# 10_-_ETHERNET.net
KiCad netlist of a schematic drawn in Altium Designer
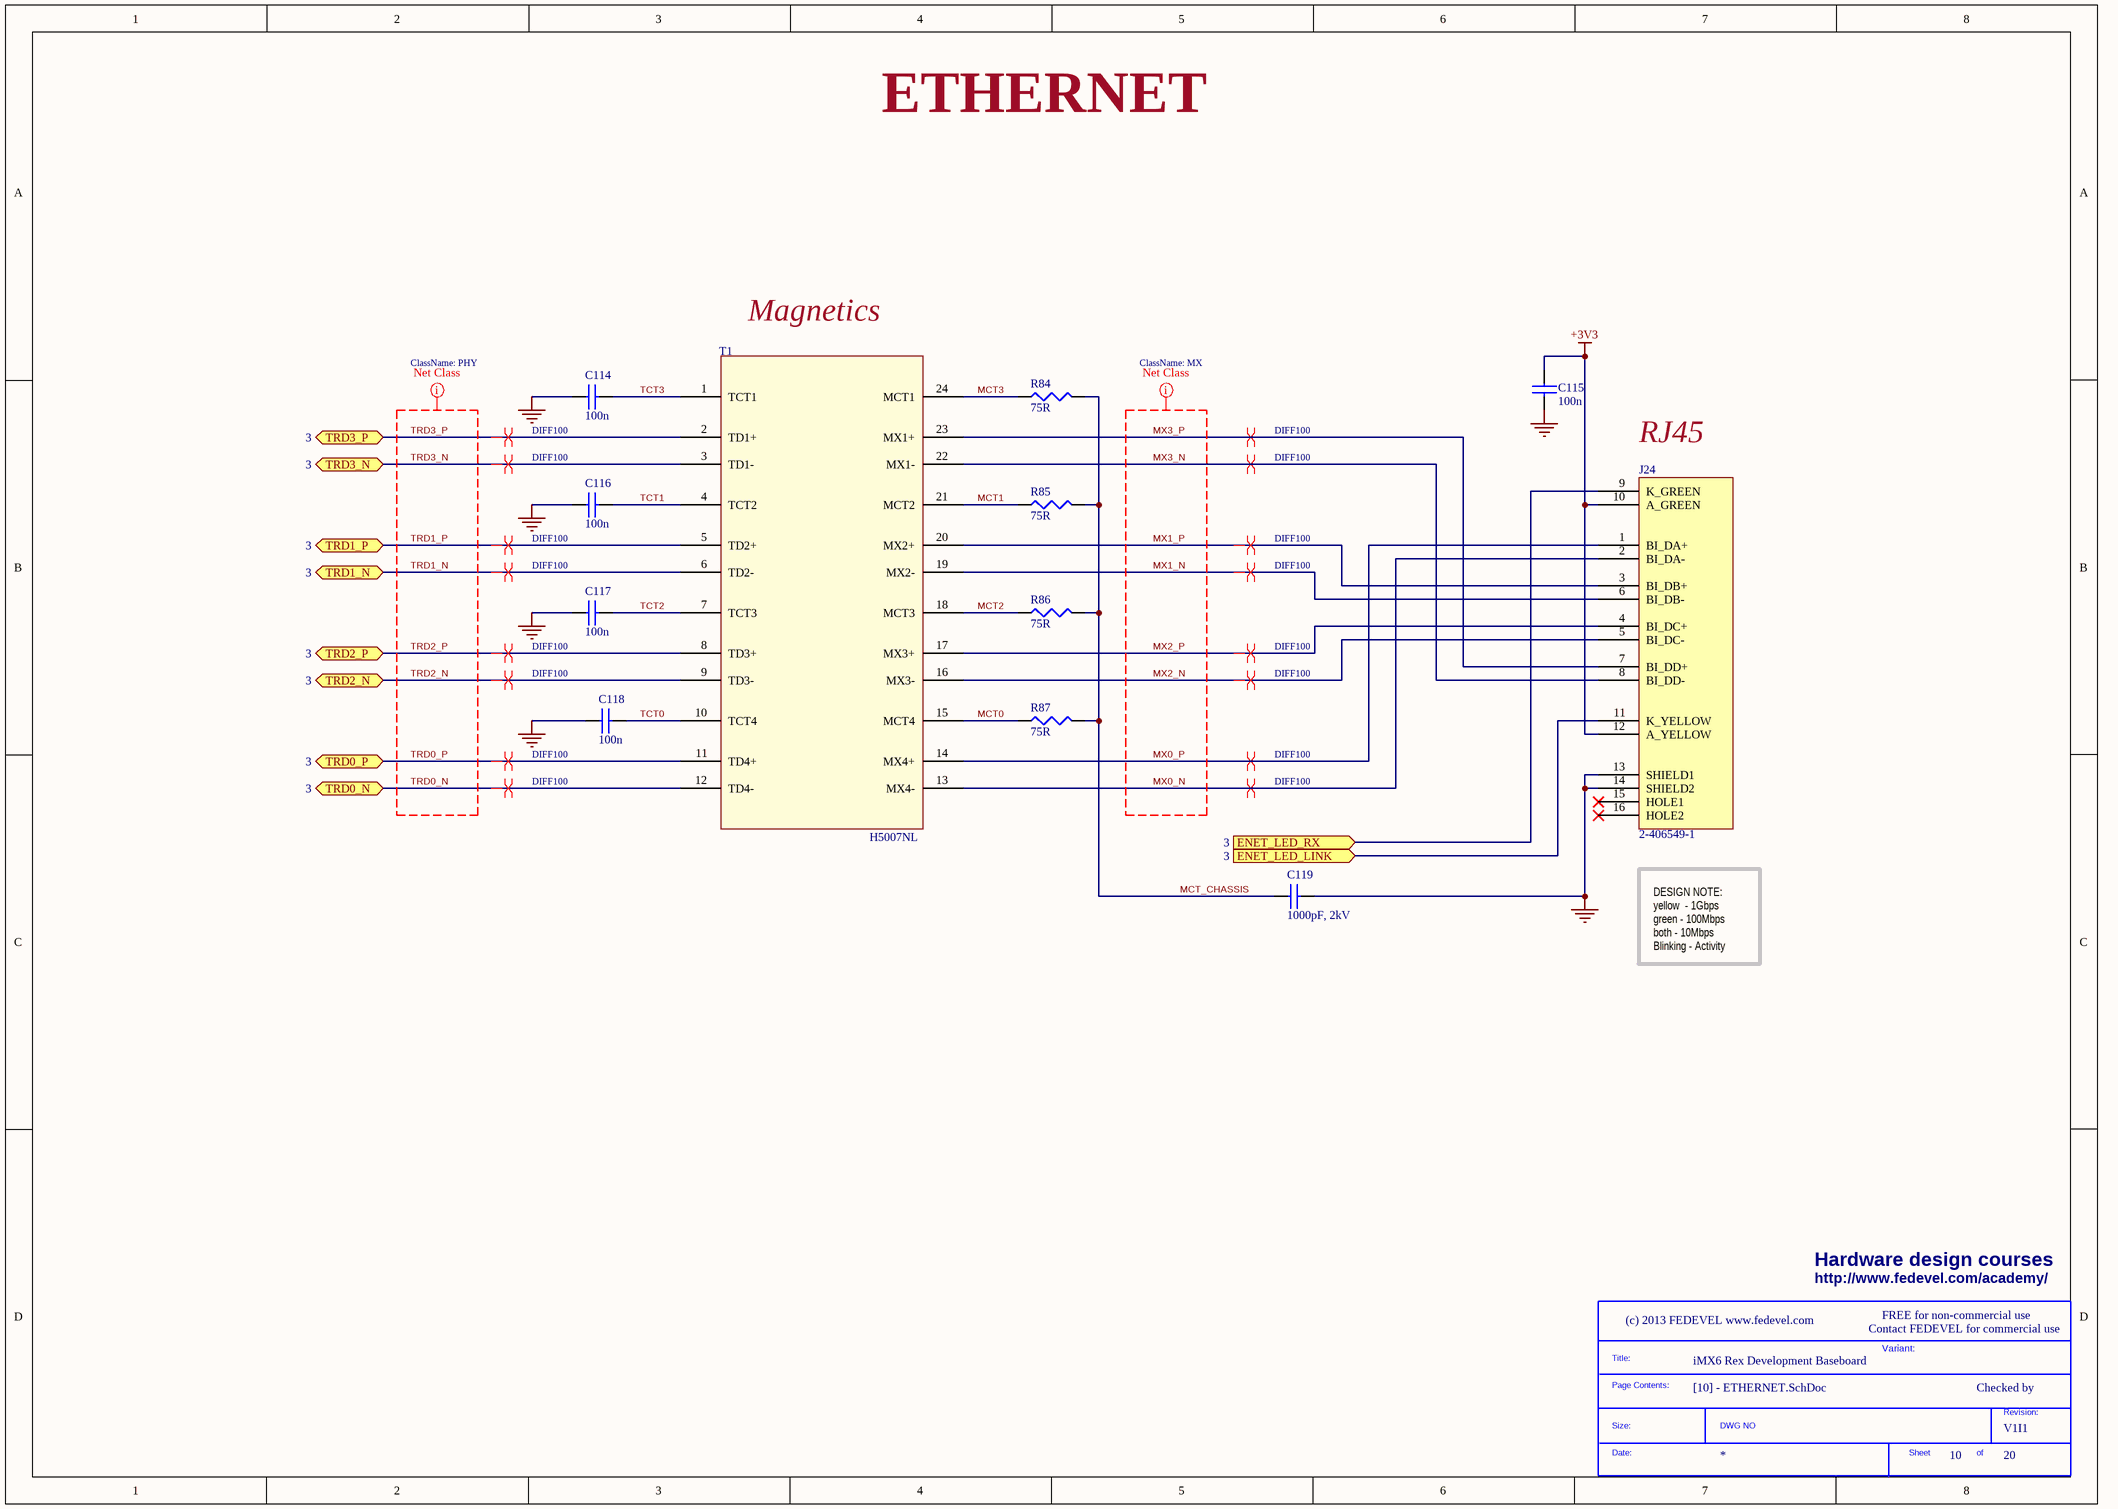
[diagram p0: [10] - ETHERNET.SchDoc]

(export (version "E")
  (design (tool "Eeschema 10.0.6"))
  (components
    (comp (ref "C114")
      (value "100n")
      (footprint "C0402")
      (description "CAP CER .10UF 50V X5R 10% 0402")
      (fields
        (field (name "MANUFACTURER") "TDK Corporation")
        (field (name "MANUFACTURER PART NUMBER") "C1005X5R1H104K")
      )
      (libsource (lib "Integrated_Library_RF_FEB_2012") (part "C1005X5R1H104K"))
    )
    (comp (ref "C115")
      (value "100n")
      (footprint "C0402")
      (description "CAP CER .10UF 50V X5R 10% 0402")
      (fields
        (field (name "MANUFACTURER") "TDK Corporation")
        (field (name "MANUFACTURER PART NUMBER") "C1005X5R1H104K")
      )
      (libsource (lib "Integrated_Library_RF_FEB_2012") (part "C1005X5R1H104K"))
    )
    (comp (ref "C116")
      (value "100n")
      (footprint "C0402")
      (description "CAP CER .10UF 50V X5R 10% 0402")
      (fields
        (field (name "MANUFACTURER") "TDK Corporation")
        (field (name "MANUFACTURER PART NUMBER") "C1005X5R1H104K")
      )
      (libsource (lib "Integrated_Library_RF_FEB_2012") (part "C1005X5R1H104K"))
    )
    (comp (ref "C117")
      (value "100n")
      (footprint "C0402")
      (description "CAP CER .10UF 50V X5R 10% 0402")
      (fields
        (field (name "MANUFACTURER") "TDK Corporation")
        (field (name "MANUFACTURER PART NUMBER") "C1005X5R1H104K")
      )
      (libsource (lib "Integrated_Library_RF_FEB_2012") (part "C1005X5R1H104K"))
    )
    (comp (ref "C118")
      (value "100n")
      (footprint "C0402")
      (description "CAP CER .10UF 50V X5R 10% 0402")
      (fields
        (field (name "MANUFACTURER") "TDK Corporation")
        (field (name "MANUFACTURER PART NUMBER") "C1005X5R1H104K")
      )
      (libsource (lib "Integrated_Library_RF_FEB_2012") (part "C1005X5R1H104K"))
    )
    (comp (ref "C119")
      (value "1000pF, 2kV")
      (footprint "C1206")
      (description "CAP CER 1000PF 2000V X7R 1206 FT")
      (fields
        (field (name "MANUFACTURER") "Kemet")
        (field (name "MANUFACTURER PART NUMBER") "C1206X102KGRACTU")
      )
      (libsource (lib "Integrated_Library_RF_FEB_2012") (part "C1206X102KGRACTU"))
    )
    (comp (ref "J24")
      (value "2-406549-1")
      (footprint "RJ45LED")
      (description "CONN MOD JACK 8POS R/A Y-G PCB")
      (fields (field (name "MANUFACTURER") "Tyco"))
      (libsource (lib "Integrated_Library_RF_FEB_2012") (part "2-406549-1"))
    )
    (comp (ref "R84")
      (value "75R")
      (footprint "R0402")
      (description "RES 75.0 OHM 1/16W 1% 0402 SMD")
      (fields
        (field (name "MANUFACTURER") "Yageo")
        (field (name "MANUFACTURER PART NUMBER") "RC0402FR-0775RL")
      )
      (libsource (lib "Integrated_Library_RF_FEB_2012") (part "RC0402FR-0775RL"))
    )
    (comp (ref "R85")
      (value "75R")
      (footprint "R0402")
      (description "RES 75.0 OHM 1/16W 1% 0402 SMD")
      (fields
        (field (name "MANUFACTURER") "Yageo")
        (field (name "MANUFACTURER PART NUMBER") "RC0402FR-0775RL")
      )
      (libsource (lib "Integrated_Library_RF_FEB_2012") (part "RC0402FR-0775RL"))
    )
    (comp (ref "R86")
      (value "75R")
      (footprint "R0402")
      (description "RES 75.0 OHM 1/16W 1% 0402 SMD")
      (fields
        (field (name "MANUFACTURER") "Yageo")
        (field (name "MANUFACTURER PART NUMBER") "RC0402FR-0775RL")
      )
      (libsource (lib "Integrated_Library_RF_FEB_2012") (part "RC0402FR-0775RL"))
    )
    (comp (ref "R87")
      (value "75R")
      (footprint "R0402")
      (description "RES 75.0 OHM 1/16W 1% 0402 SMD")
      (fields
        (field (name "MANUFACTURER") "Yageo")
        (field (name "MANUFACTURER PART NUMBER") "RC0402FR-0775RL")
      )
      (libsource (lib "Integrated_Library_RF_FEB_2012") (part "RC0402FR-0775RL"))
    )
    (comp (ref "T1")
      (value "H5007NL")
      (footprint "H5007NL")
      (description "MODULE SINGLE GIGABIT LAN 24SOIC")
      (fields
        (field (name "MANUFACTURER") "PULSE ELECTRONICS CORPORATION")
        (field (name ".CHECKED PCB") "MM")
        (field (name ".CHECKED SCH") "MM")
      )
      (libsource (lib "Integrated_Library_RF_FEB_2012") (part "H5007NL"))
    )
  )
  (nets
    (net (code "1") (name "+3V3") (class "Default")
      (node (ref "C115") (pin "1") (pinfunction "1_1") (pintype "passive"))
      (node (ref "J24") (pin "10") (pinfunction "A_GREEN_10") (pintype "passive"))
      (node (ref "J24") (pin "12") (pinfunction "A_YELLOW_12") (pintype "passive"))
    )
    (net (code "2") (name "/ENET_LED_LINK") (class "Default")
      (node (ref "J24") (pin "11") (pinfunction "K_YELLOW_11") (pintype "passive"))
    )
    (net (code "3") (name "/ENET_LED_RX") (class "Default")
      (node (ref "J24") (pin "9") (pinfunction "K_GREEN_9") (pintype "passive"))
    )
    (net (code "4") (name "/MCT0") (class "Default")
      (node (ref "R87") (pin "1") (pinfunction "1_1") (pintype "passive"))
      (node (ref "T1") (pin "15") (pinfunction "MCT4_15") (pintype "passive"))
    )
    (net (code "5") (name "/MCT1") (class "Default")
      (node (ref "R85") (pin "1") (pinfunction "1_1") (pintype "passive"))
      (node (ref "T1") (pin "21") (pinfunction "MCT2_21") (pintype "passive"))
    )
    (net (code "6") (name "/MCT2") (class "Default")
      (node (ref "R86") (pin "1") (pinfunction "1_1") (pintype "passive"))
      (node (ref "T1") (pin "18") (pinfunction "MCT3_18") (pintype "passive"))
    )
    (net (code "7") (name "/MCT3") (class "Default")
      (node (ref "R84") (pin "1") (pinfunction "1_1") (pintype "passive"))
      (node (ref "T1") (pin "24") (pinfunction "MCT1_24") (pintype "passive"))
    )
    (net (code "8") (name "/MCT_CHASSIS") (class "Default")
      (node (ref "C119") (pin "1") (pinfunction "1_1") (pintype "passive"))
      (node (ref "R84") (pin "2") (pinfunction "2_2") (pintype "passive"))
      (node (ref "R85") (pin "2") (pinfunction "2_2") (pintype "passive"))
      (node (ref "R86") (pin "2") (pinfunction "2_2") (pintype "passive"))
      (node (ref "R87") (pin "2") (pinfunction "2_2") (pintype "passive"))
    )
    (net (code "9") (name "/MX0_N") (class "Default")
      (node (ref "J24") (pin "2") (pinfunction "BI_DA-_2") (pintype "passive"))
      (node (ref "T1") (pin "13") (pinfunction "MX4-_13") (pintype "passive"))
    )
    (net (code "10") (name "/MX0_P") (class "Default")
      (node (ref "J24") (pin "1") (pinfunction "BI_DA+_1") (pintype "passive"))
      (node (ref "T1") (pin "14") (pinfunction "MX4+_14") (pintype "passive"))
    )
    (net (code "11") (name "/MX1_N") (class "Default")
      (node (ref "J24") (pin "6") (pinfunction "BI_DB-_6") (pintype "passive"))
      (node (ref "T1") (pin "19") (pinfunction "MX2-_19") (pintype "passive"))
    )
    (net (code "12") (name "/MX1_P") (class "Default")
      (node (ref "J24") (pin "3") (pinfunction "BI_DB+_3") (pintype "passive"))
      (node (ref "T1") (pin "20") (pinfunction "MX2+_20") (pintype "passive"))
    )
    (net (code "13") (name "/MX2_N") (class "Default")
      (node (ref "J24") (pin "5") (pinfunction "BI_DC-_5") (pintype "passive"))
      (node (ref "T1") (pin "16") (pinfunction "MX3-_16") (pintype "passive"))
    )
    (net (code "14") (name "/MX2_P") (class "Default")
      (node (ref "J24") (pin "4") (pinfunction "BI_DC+_4") (pintype "passive"))
      (node (ref "T1") (pin "17") (pinfunction "MX3+_17") (pintype "passive"))
    )
    (net (code "15") (name "/MX3_N") (class "Default")
      (node (ref "J24") (pin "8") (pinfunction "BI_DD-_8") (pintype "passive"))
      (node (ref "T1") (pin "22") (pinfunction "MX1-_22") (pintype "passive"))
    )
    (net (code "16") (name "/MX3_P") (class "Default")
      (node (ref "J24") (pin "7") (pinfunction "BI_DD+_7") (pintype "passive"))
      (node (ref "T1") (pin "23") (pinfunction "MX1+_23") (pintype "passive"))
    )
    (net (code "17") (name "/TCT0") (class "Default")
      (node (ref "C118") (pin "2") (pinfunction "2_2") (pintype "passive"))
      (node (ref "T1") (pin "10") (pinfunction "TCT4_10") (pintype "passive"))
    )
    (net (code "18") (name "/TCT1") (class "Default")
      (node (ref "C116") (pin "2") (pinfunction "2_2") (pintype "passive"))
      (node (ref "T1") (pin "4") (pinfunction "TCT2_4") (pintype "passive"))
    )
    (net (code "19") (name "/TCT2") (class "Default")
      (node (ref "C117") (pin "2") (pinfunction "2_2") (pintype "passive"))
      (node (ref "T1") (pin "7") (pinfunction "TCT3_7") (pintype "passive"))
    )
    (net (code "20") (name "/TCT3") (class "Default")
      (node (ref "C114") (pin "2") (pinfunction "2_2") (pintype "passive"))
      (node (ref "T1") (pin "1") (pinfunction "TCT1_1") (pintype "passive"))
    )
    (net (code "21") (name "/TRD0_N") (class "Default")
      (node (ref "T1") (pin "12") (pinfunction "TD4-_12") (pintype "passive"))
    )
    (net (code "22") (name "/TRD0_P") (class "Default")
      (node (ref "T1") (pin "11") (pinfunction "TD4+_11") (pintype "passive"))
    )
    (net (code "23") (name "/TRD1_N") (class "Default")
      (node (ref "T1") (pin "6") (pinfunction "TD2-_6") (pintype "passive"))
    )
    (net (code "24") (name "/TRD1_P") (class "Default")
      (node (ref "T1") (pin "5") (pinfunction "TD2+_5") (pintype "passive"))
    )
    (net (code "25") (name "/TRD2_N") (class "Default")
      (node (ref "T1") (pin "9") (pinfunction "TD3-_9") (pintype "passive"))
    )
    (net (code "26") (name "/TRD2_P") (class "Default")
      (node (ref "T1") (pin "8") (pinfunction "TD3+_8") (pintype "passive"))
    )
    (net (code "27") (name "/TRD3_N") (class "Default")
      (node (ref "T1") (pin "3") (pinfunction "TD1-_3") (pintype "passive"))
    )
    (net (code "28") (name "/TRD3_P") (class "Default")
      (node (ref "T1") (pin "2") (pinfunction "TD1+_2") (pintype "passive"))
    )
    (net (code "29") (name "GND") (class "Default")
      (node (ref "C114") (pin "1") (pinfunction "1_1") (pintype "passive"))
      (node (ref "C115") (pin "2") (pinfunction "2_2") (pintype "passive"))
      (node (ref "C116") (pin "1") (pinfunction "1_1") (pintype "passive"))
      (node (ref "C117") (pin "1") (pinfunction "1_1") (pintype "passive"))
      (node (ref "C118") (pin "1") (pinfunction "1_1") (pintype "passive"))
      (node (ref "C119") (pin "2") (pinfunction "2_2") (pintype "passive"))
      (node (ref "J24") (pin "13") (pinfunction "SHIELD1_13") (pintype "passive"))
      (node (ref "J24") (pin "14") (pinfunction "SHIELD2_14") (pintype "passive"))
    )
    (net (code "30") (name "unconnected-(J24-HOLE1-Pad15)") (class "Default")
      (node (ref "J24") (pin "15") (pinfunction "HOLE1_15") (pintype "passive+no_connect"))
    )
    (net (code "31") (name "unconnected-(J24-HOLE2-Pad16)") (class "Default")
      (node (ref "J24") (pin "16") (pinfunction "HOLE2_16") (pintype "passive+no_connect"))
    )
  )
)
